# MBO.net
KiCad netlist of a schematic drawn in EAGLE
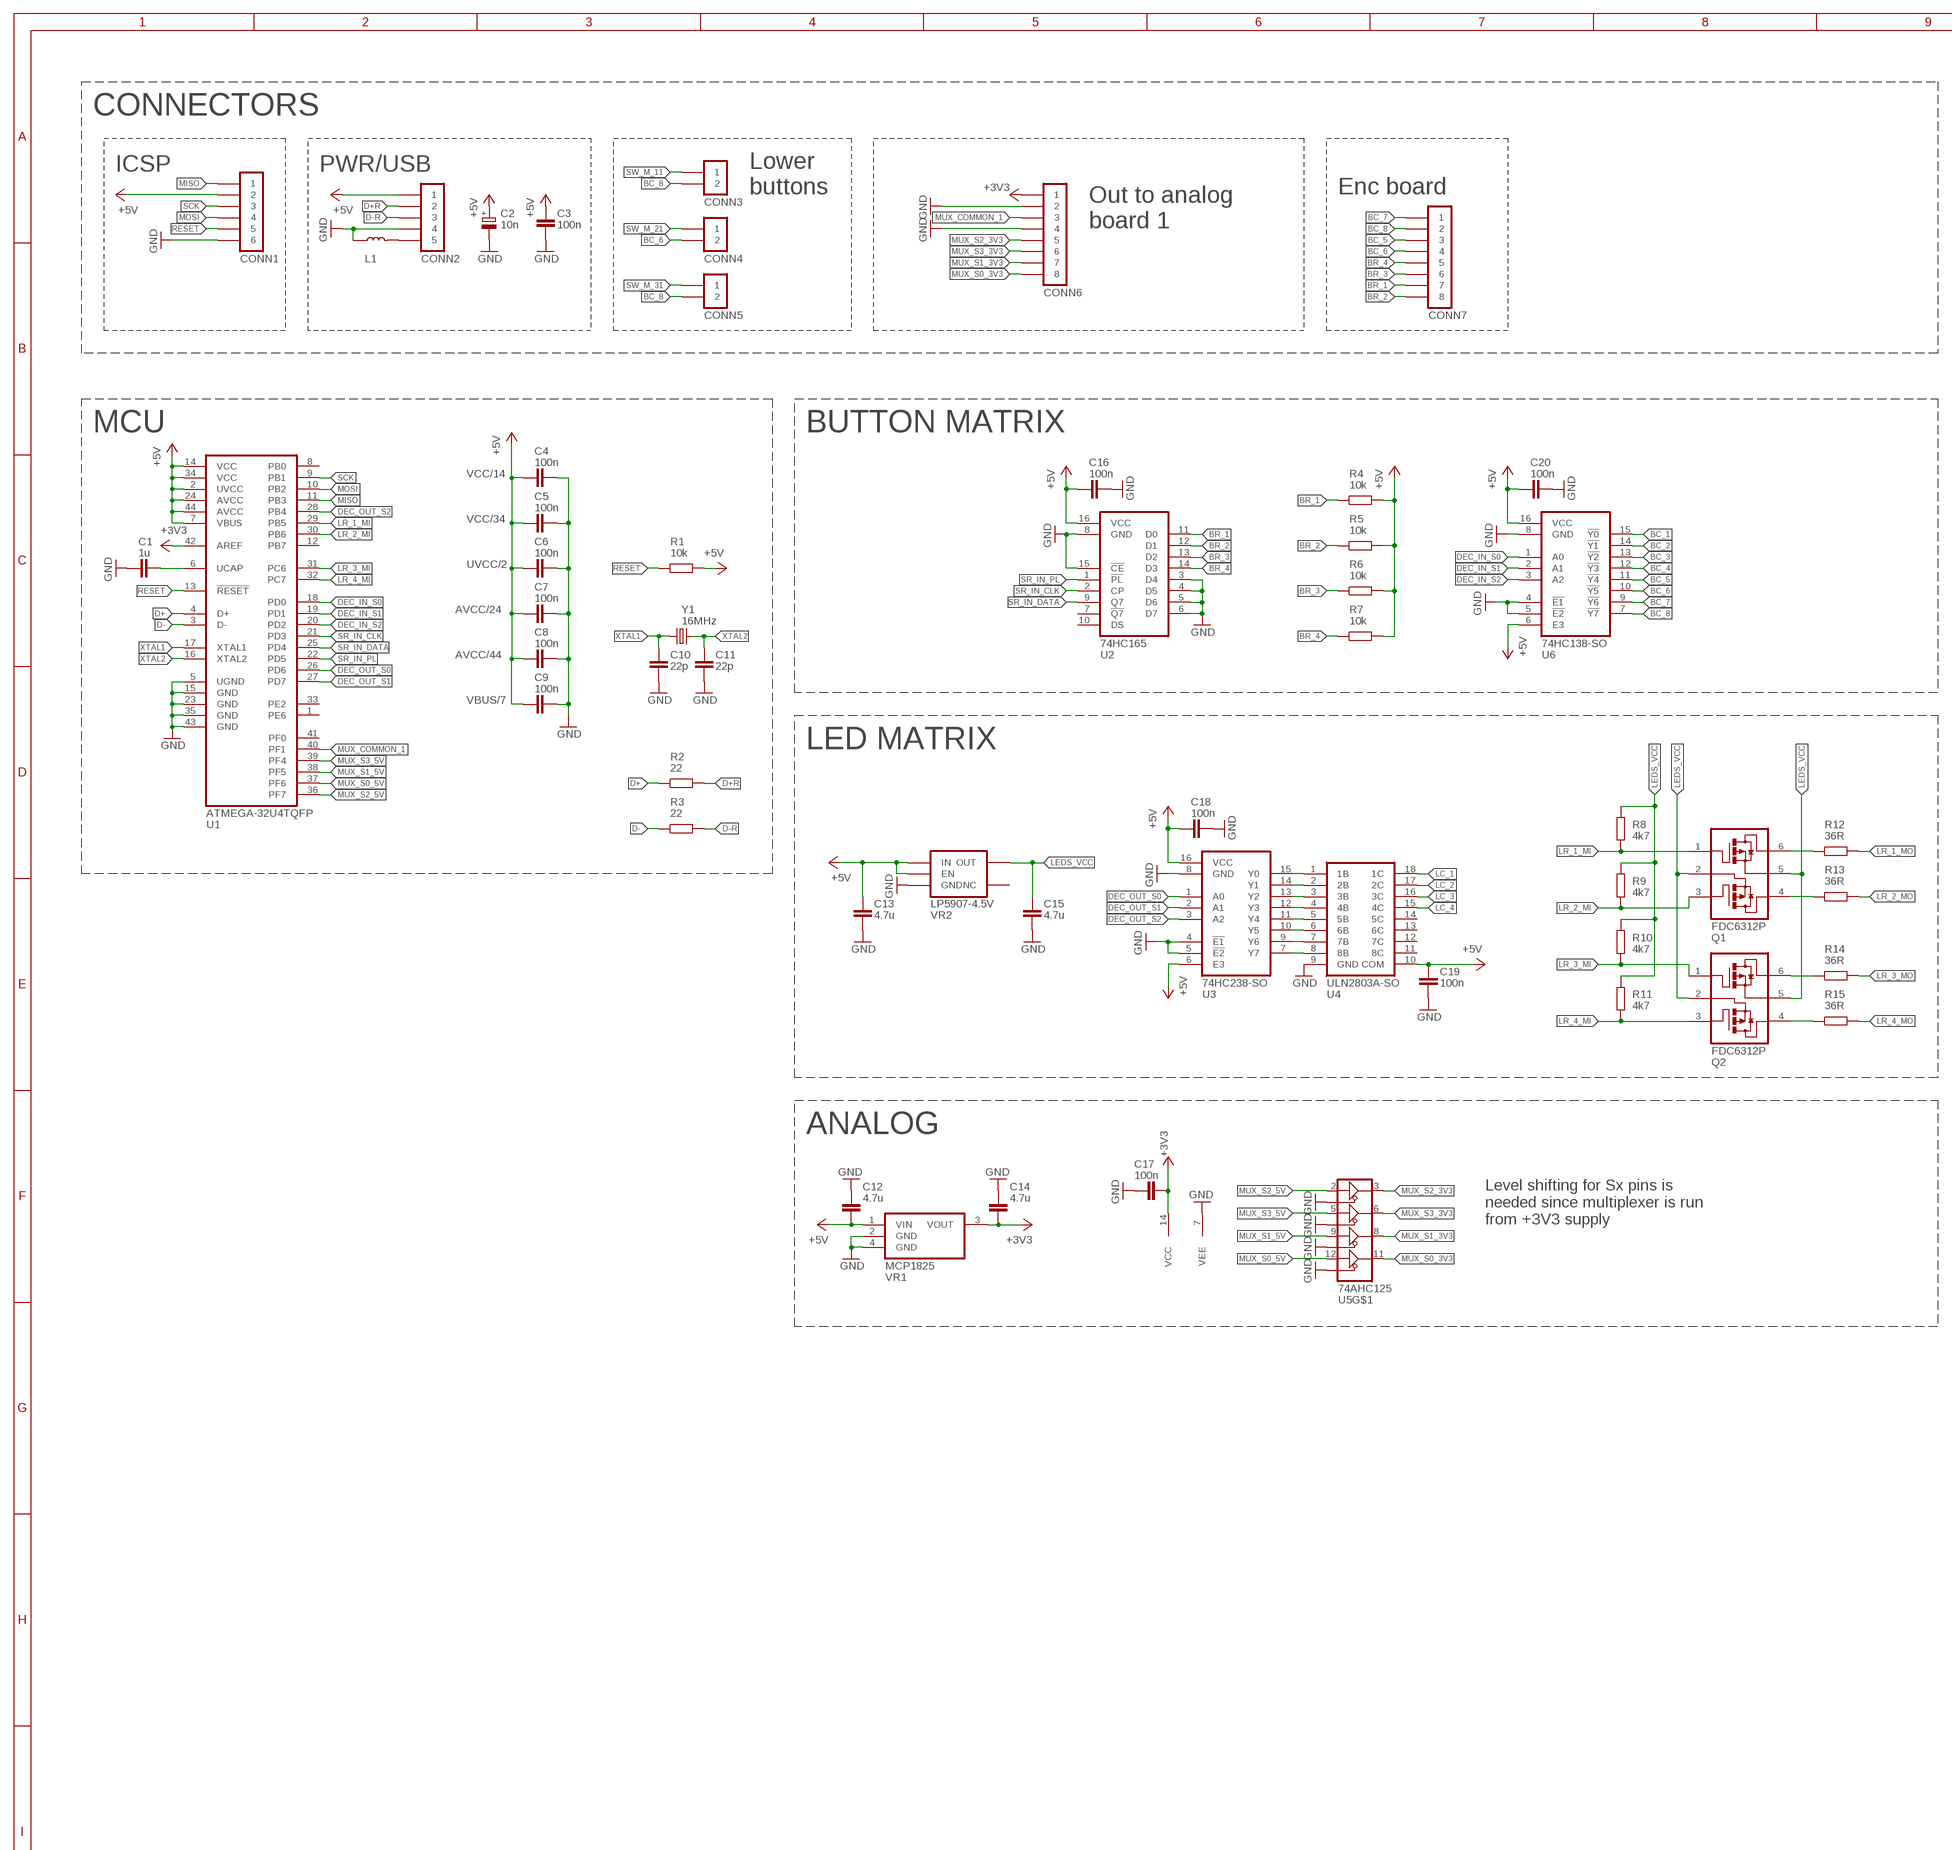
[diagram p0: schematic, sheet 1, part 1 of 2]
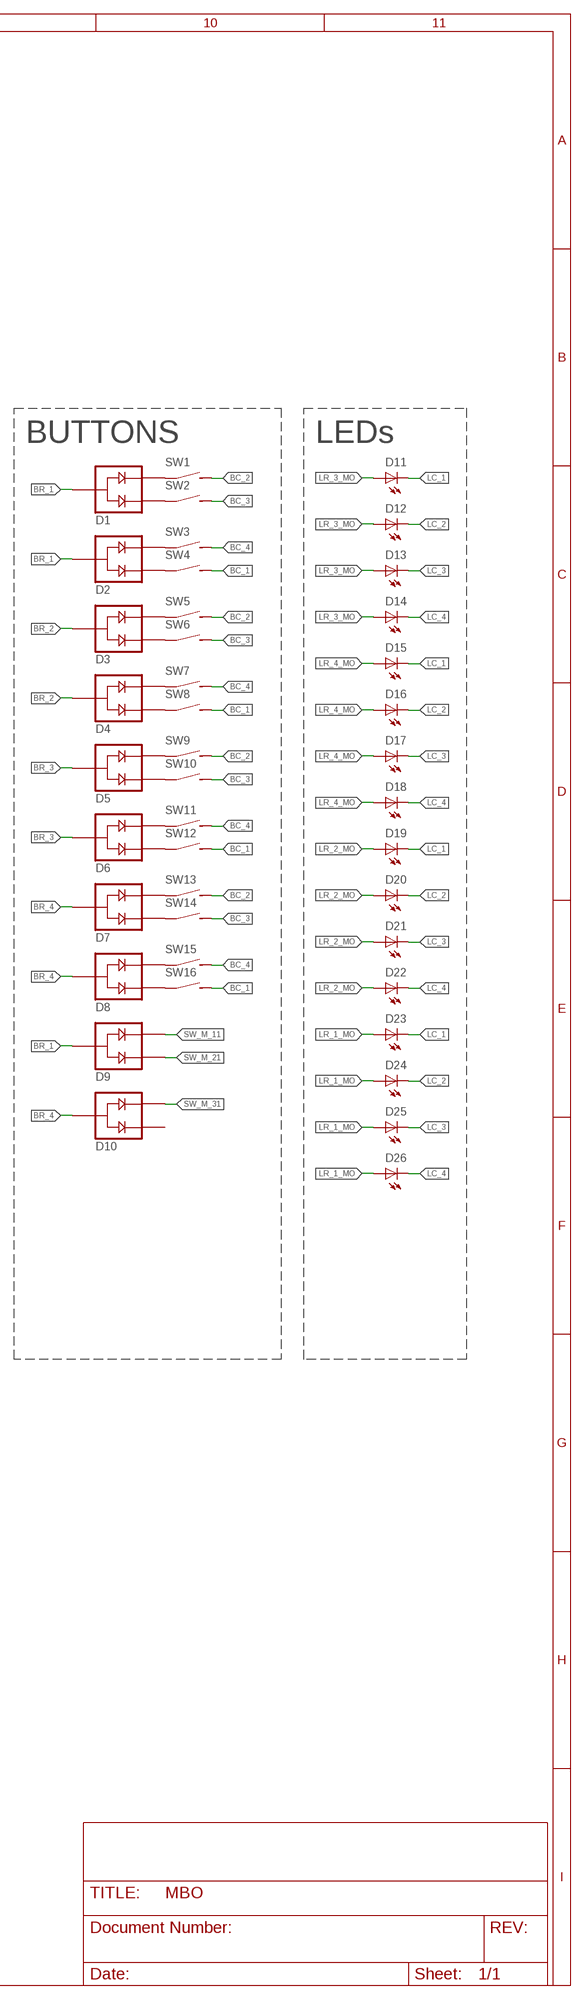
[diagram p1: schematic, sheet 1, part 2 of 2]

(export (version "E")
  (design (tool "Eeschema 10.0.6"))
  (components
    (comp (ref "C1")
      (value "1u")
      (footprint "eagle-import:C0805")
      (libsource (lib "eagle-import") (part "CAPACITOR-0805"))
    )
    (comp (ref "C2")
      (value "10n")
      (footprint "eagle-import:153CLV-0405")
      (fields (field (name "MANUFACTURER") "Multicomp") (field (name "MPN") "MCVVT016M100CA1L"))
      (libsource (lib "eagle-import") (part "ELECTROLYTIC_CAPACITOR-CLV-040516V"))
    )
    (comp (ref "C3")
      (value "100n")
      (footprint "eagle-import:C0805")
      (libsource (lib "eagle-import") (part "CAPACITOR-0805"))
    )
    (comp (ref "C4")
      (value "100n")
      (footprint "eagle-import:C0805")
      (libsource (lib "eagle-import") (part "CAPACITOR-0805"))
    )
    (comp (ref "C5")
      (value "100n")
      (footprint "eagle-import:C0805")
      (libsource (lib "eagle-import") (part "CAPACITOR-0805"))
    )
    (comp (ref "C6")
      (value "100n")
      (footprint "eagle-import:C0805")
      (libsource (lib "eagle-import") (part "CAPACITOR-0805"))
    )
    (comp (ref "C7")
      (value "100n")
      (footprint "eagle-import:C0805")
      (libsource (lib "eagle-import") (part "CAPACITOR-0805"))
    )
    (comp (ref "C8")
      (value "100n")
      (footprint "eagle-import:C0805")
      (libsource (lib "eagle-import") (part "CAPACITOR-0805"))
    )
    (comp (ref "C9")
      (value "100n")
      (footprint "eagle-import:C0805")
      (libsource (lib "eagle-import") (part "CAPACITOR-0805"))
    )
    (comp (ref "C10")
      (value "22p")
      (footprint "eagle-import:C0805")
      (libsource (lib "eagle-import") (part "CAPACITOR-0805"))
    )
    (comp (ref "C11")
      (value "22p")
      (footprint "eagle-import:C0805")
      (libsource (lib "eagle-import") (part "CAPACITOR-0805"))
    )
    (comp (ref "C12")
      (value "4.7u")
      (footprint "eagle-import:C0805")
      (libsource (lib "eagle-import") (part "CAPACITOR-0805"))
    )
    (comp (ref "C13")
      (value "4.7u")
      (footprint "eagle-import:C0805")
      (libsource (lib "eagle-import") (part "CAPACITOR-0805"))
    )
    (comp (ref "C14")
      (value "4.7u")
      (footprint "eagle-import:C0805")
      (libsource (lib "eagle-import") (part "CAPACITOR-0805"))
    )
    (comp (ref "C15")
      (value "4.7u")
      (footprint "eagle-import:C0805")
      (libsource (lib "eagle-import") (part "CAPACITOR-0805"))
    )
    (comp (ref "C16")
      (value "100n")
      (footprint "eagle-import:C0805")
      (libsource (lib "eagle-import") (part "CAPACITOR-0805"))
    )
    (comp (ref "C17")
      (value "100n")
      (footprint "eagle-import:C0805")
      (libsource (lib "eagle-import") (part "CAPACITOR-0805"))
    )
    (comp (ref "C18")
      (value "100n")
      (footprint "eagle-import:C0805")
      (libsource (lib "eagle-import") (part "CAPACITOR-0805"))
    )
    (comp (ref "C19")
      (value "100n")
      (footprint "eagle-import:C0805")
      (libsource (lib "eagle-import") (part "CAPACITOR-0805"))
    )
    (comp (ref "C20")
      (value "100n")
      (footprint "eagle-import:C0805")
      (libsource (lib "eagle-import") (part "CAPACITOR-0805"))
    )
    (comp (ref "CONN1")
      (value "PINHD-2X03-TH-2.54MM-V")
      (footprint "eagle-import:2X03-2.54-V")
      (libsource (lib "eagle-import") (part "PINHD-2X03-TH-2.54MM-V"))
    )
    (comp (ref "CONN2")
      (value "PINHD-1X05-JST-XH-H")
      (footprint "eagle-import:JST-XH-05P-H")
      (libsource (lib "eagle-import") (part "PINHD-1X05-JST-XH-H"))
    )
    (comp (ref "CONN3")
      (value "PINHD-1X02-JST-XH-H")
      (footprint "eagle-import:JST-XH-02P-H")
      (libsource (lib "eagle-import") (part "PINHD-1X02-JST-XH-H"))
    )
    (comp (ref "CONN4")
      (value "PINHD-1X02-JST-XH-H")
      (footprint "eagle-import:JST-XH-02P-H")
      (libsource (lib "eagle-import") (part "PINHD-1X02-JST-XH-H"))
    )
    (comp (ref "CONN5")
      (value "PINHD-1X02-JST-XH-H")
      (footprint "eagle-import:JST-XH-02P-H")
      (libsource (lib "eagle-import") (part "PINHD-1X02-JST-XH-H"))
    )
    (comp (ref "CONN6")
      (value "PINHD-2X04-IDC-2.54-V")
      (footprint "eagle-import:IDC-08P-2.54")
      (libsource (lib "eagle-import") (part "PINHD-2X04-IDC-2.54-V"))
    )
    (comp (ref "CONN7")
      (value "PINHD-1X08-FFC-1MM")
      (footprint "eagle-import:MOLEX-52793-0870")
      (libsource (lib "eagle-import") (part "PINHD-1X08-FFC-1MM"))
    )
    (comp (ref "D1")
      (value "BAW56")
      (footprint "eagle-import:SOT23")
      (fields (field (name "MANUFACTURER") "Multicomp") (field (name "MPN") "BAW56-7-F"))
      (libsource (lib "eagle-import") (part "BAW56"))
    )
    (comp (ref "D2")
      (value "BAW56")
      (footprint "eagle-import:SOT23")
      (fields (field (name "MANUFACTURER") "Multicomp") (field (name "MPN") "BAW56-7-F"))
      (libsource (lib "eagle-import") (part "BAW56"))
    )
    (comp (ref "D3")
      (value "BAW56")
      (footprint "eagle-import:SOT23")
      (fields (field (name "MANUFACTURER") "Multicomp") (field (name "MPN") "BAW56-7-F"))
      (libsource (lib "eagle-import") (part "BAW56"))
    )
    (comp (ref "D4")
      (value "BAW56")
      (footprint "eagle-import:SOT23")
      (fields (field (name "MANUFACTURER") "Multicomp") (field (name "MPN") "BAW56-7-F"))
      (libsource (lib "eagle-import") (part "BAW56"))
    )
    (comp (ref "D5")
      (value "BAW56")
      (footprint "eagle-import:SOT23")
      (fields (field (name "MANUFACTURER") "Multicomp") (field (name "MPN") "BAW56-7-F"))
      (libsource (lib "eagle-import") (part "BAW56"))
    )
    (comp (ref "D6")
      (value "BAW56")
      (footprint "eagle-import:SOT23")
      (fields (field (name "MANUFACTURER") "Multicomp") (field (name "MPN") "BAW56-7-F"))
      (libsource (lib "eagle-import") (part "BAW56"))
    )
    (comp (ref "D7")
      (value "BAW56")
      (footprint "eagle-import:SOT23")
      (fields (field (name "MANUFACTURER") "Multicomp") (field (name "MPN") "BAW56-7-F"))
      (libsource (lib "eagle-import") (part "BAW56"))
    )
    (comp (ref "D8")
      (value "BAW56")
      (footprint "eagle-import:SOT23")
      (fields (field (name "MANUFACTURER") "Multicomp") (field (name "MPN") "BAW56-7-F"))
      (libsource (lib "eagle-import") (part "BAW56"))
    )
    (comp (ref "D9")
      (value "BAW56")
      (footprint "eagle-import:SOT23")
      (fields (field (name "MANUFACTURER") "Multicomp") (field (name "MPN") "BAW56-7-F"))
      (libsource (lib "eagle-import") (part "BAW56"))
    )
    (comp (ref "D10")
      (value "BAW56")
      (footprint "eagle-import:SOT23")
      (fields (field (name "MANUFACTURER") "Multicomp") (field (name "MPN") "BAW56-7-F"))
      (libsource (lib "eagle-import") (part "BAW56"))
    )
    (comp (ref "D11")
      (value "LED-0805")
      (footprint "eagle-import:0805_LED")
      (libsource (lib "eagle-import") (part "LED-0805"))
    )
    (comp (ref "D12")
      (value "LED-0805")
      (footprint "eagle-import:0805_LED")
      (libsource (lib "eagle-import") (part "LED-0805"))
    )
    (comp (ref "D13")
      (value "LED-0805")
      (footprint "eagle-import:0805_LED")
      (libsource (lib "eagle-import") (part "LED-0805"))
    )
    (comp (ref "D14")
      (value "LED-0805")
      (footprint "eagle-import:0805_LED")
      (libsource (lib "eagle-import") (part "LED-0805"))
    )
    (comp (ref "D15")
      (value "LED-0805")
      (footprint "eagle-import:0805_LED")
      (libsource (lib "eagle-import") (part "LED-0805"))
    )
    (comp (ref "D16")
      (value "LED-0805")
      (footprint "eagle-import:0805_LED")
      (libsource (lib "eagle-import") (part "LED-0805"))
    )
    (comp (ref "D17")
      (value "LED-0805")
      (footprint "eagle-import:0805_LED")
      (libsource (lib "eagle-import") (part "LED-0805"))
    )
    (comp (ref "D18")
      (value "LED-0805")
      (footprint "eagle-import:0805_LED")
      (libsource (lib "eagle-import") (part "LED-0805"))
    )
    (comp (ref "D19")
      (value "LED-0805")
      (footprint "eagle-import:0805_LED")
      (libsource (lib "eagle-import") (part "LED-0805"))
    )
    (comp (ref "D20")
      (value "LED-0805")
      (footprint "eagle-import:0805_LED")
      (libsource (lib "eagle-import") (part "LED-0805"))
    )
    (comp (ref "D21")
      (value "LED-0805")
      (footprint "eagle-import:0805_LED")
      (libsource (lib "eagle-import") (part "LED-0805"))
    )
    (comp (ref "D22")
      (value "LED-0805")
      (footprint "eagle-import:0805_LED")
      (libsource (lib "eagle-import") (part "LED-0805"))
    )
    (comp (ref "D23")
      (value "LED-0805")
      (footprint "eagle-import:0805_LED")
      (libsource (lib "eagle-import") (part "LED-0805"))
    )
    (comp (ref "D24")
      (value "LED-0805")
      (footprint "eagle-import:0805_LED")
      (libsource (lib "eagle-import") (part "LED-0805"))
    )
    (comp (ref "D25")
      (value "LED-0805")
      (footprint "eagle-import:0805_LED")
      (libsource (lib "eagle-import") (part "LED-0805"))
    )
    (comp (ref "D26")
      (value "LED-0805")
      (footprint "eagle-import:0805_LED")
      (libsource (lib "eagle-import") (part "LED-0805"))
    )
    (comp (ref "L1")
      (value "INDUCTOR-0805")
      (footprint "eagle-import:L0805")
      (libsource (lib "eagle-import") (part "INDUCTOR-0805"))
    )
    (comp (ref "Q1")
      (value "FDC6312P")
      (footprint "eagle-import:SSOT6")
      (fields (field (name "MANUFACTURER") "ON Semiconductor"))
      (libsource (lib "eagle-import") (part "FDC6312P"))
    )
    (comp (ref "Q2")
      (value "FDC6312P")
      (footprint "eagle-import:SSOT6")
      (fields (field (name "MANUFACTURER") "ON Semiconductor"))
      (libsource (lib "eagle-import") (part "FDC6312P"))
    )
    (comp (ref "R1")
      (value "10k")
      (footprint "eagle-import:R0805")
      (libsource (lib "eagle-import") (part "RESISTOR-0805"))
    )
    (comp (ref "R2")
      (value "22")
      (footprint "eagle-import:R0805")
      (libsource (lib "eagle-import") (part "RESISTOR-0805"))
    )
    (comp (ref "R3")
      (value "22")
      (footprint "eagle-import:R0805")
      (libsource (lib "eagle-import") (part "RESISTOR-0805"))
    )
    (comp (ref "R4")
      (value "10k")
      (footprint "eagle-import:R0805")
      (libsource (lib "eagle-import") (part "RESISTOR-0805"))
    )
    (comp (ref "R5")
      (value "10k")
      (footprint "eagle-import:R0805")
      (libsource (lib "eagle-import") (part "RESISTOR-0805"))
    )
    (comp (ref "R6")
      (value "10k")
      (footprint "eagle-import:R0805")
      (libsource (lib "eagle-import") (part "RESISTOR-0805"))
    )
    (comp (ref "R7")
      (value "10k")
      (footprint "eagle-import:R0805")
      (libsource (lib "eagle-import") (part "RESISTOR-0805"))
    )
    (comp (ref "R8")
      (value "4k7")
      (footprint "eagle-import:R0805")
      (libsource (lib "eagle-import") (part "RESISTOR-0805"))
    )
    (comp (ref "R9")
      (value "4k7")
      (footprint "eagle-import:R0805")
      (libsource (lib "eagle-import") (part "RESISTOR-0805"))
    )
    (comp (ref "R10")
      (value "4k7")
      (footprint "eagle-import:R0805")
      (libsource (lib "eagle-import") (part "RESISTOR-0805"))
    )
    (comp (ref "R11")
      (value "4k7")
      (footprint "eagle-import:R0805")
      (libsource (lib "eagle-import") (part "RESISTOR-0805"))
    )
    (comp (ref "R12")
      (value "36R")
      (footprint "eagle-import:R0805")
      (libsource (lib "eagle-import") (part "RESISTOR-0805"))
    )
    (comp (ref "R13")
      (value "36R")
      (footprint "eagle-import:R0805")
      (libsource (lib "eagle-import") (part "RESISTOR-0805"))
    )
    (comp (ref "R14")
      (value "36R")
      (footprint "eagle-import:R0805")
      (libsource (lib "eagle-import") (part "RESISTOR-0805"))
    )
    (comp (ref "R15")
      (value "36R")
      (footprint "eagle-import:R0805")
      (libsource (lib "eagle-import") (part "RESISTOR-0805"))
    )
    (comp (ref "SW1")
      (value "SWITCH-RUBBER2")
      (footprint "eagle-import:RUBBER_SWITCH_2")
      (libsource (lib "eagle-import") (part "SWITCH-RUBBER2"))
    )
    (comp (ref "SW2")
      (value "SWITCH-RUBBER2")
      (footprint "eagle-import:RUBBER_SWITCH_2")
      (libsource (lib "eagle-import") (part "SWITCH-RUBBER2"))
    )
    (comp (ref "SW3")
      (value "SWITCH-RUBBER2")
      (footprint "eagle-import:RUBBER_SWITCH_2")
      (libsource (lib "eagle-import") (part "SWITCH-RUBBER2"))
    )
    (comp (ref "SW4")
      (value "SWITCH-RUBBER2")
      (footprint "eagle-import:RUBBER_SWITCH_2")
      (libsource (lib "eagle-import") (part "SWITCH-RUBBER2"))
    )
    (comp (ref "SW5")
      (value "SWITCH-RUBBER2")
      (footprint "eagle-import:RUBBER_SWITCH_2")
      (libsource (lib "eagle-import") (part "SWITCH-RUBBER2"))
    )
    (comp (ref "SW6")
      (value "SWITCH-RUBBER2")
      (footprint "eagle-import:RUBBER_SWITCH_2")
      (libsource (lib "eagle-import") (part "SWITCH-RUBBER2"))
    )
    (comp (ref "SW7")
      (value "SWITCH-RUBBER2")
      (footprint "eagle-import:RUBBER_SWITCH_2")
      (libsource (lib "eagle-import") (part "SWITCH-RUBBER2"))
    )
    (comp (ref "SW8")
      (value "SWITCH-RUBBER2")
      (footprint "eagle-import:RUBBER_SWITCH_2")
      (libsource (lib "eagle-import") (part "SWITCH-RUBBER2"))
    )
    (comp (ref "SW9")
      (value "SWITCH-RUBBER2")
      (footprint "eagle-import:RUBBER_SWITCH_2")
      (libsource (lib "eagle-import") (part "SWITCH-RUBBER2"))
    )
    (comp (ref "SW10")
      (value "SWITCH-RUBBER2")
      (footprint "eagle-import:RUBBER_SWITCH_2")
      (libsource (lib "eagle-import") (part "SWITCH-RUBBER2"))
    )
    (comp (ref "SW11")
      (value "SWITCH-RUBBER2")
      (footprint "eagle-import:RUBBER_SWITCH_2")
      (libsource (lib "eagle-import") (part "SWITCH-RUBBER2"))
    )
    (comp (ref "SW12")
      (value "SWITCH-RUBBER2")
      (footprint "eagle-import:RUBBER_SWITCH_2")
      (libsource (lib "eagle-import") (part "SWITCH-RUBBER2"))
    )
    (comp (ref "SW13")
      (value "SWITCH-RUBBER2")
      (footprint "eagle-import:RUBBER_SWITCH_2")
      (libsource (lib "eagle-import") (part "SWITCH-RUBBER2"))
    )
    (comp (ref "SW14")
      (value "SWITCH-RUBBER2")
      (footprint "eagle-import:RUBBER_SWITCH_2")
      (libsource (lib "eagle-import") (part "SWITCH-RUBBER2"))
    )
    (comp (ref "SW15")
      (value "SWITCH-RUBBER2")
      (footprint "eagle-import:RUBBER_SWITCH_2")
      (libsource (lib "eagle-import") (part "SWITCH-RUBBER2"))
    )
    (comp (ref "SW16")
      (value "SWITCH-RUBBER2")
      (footprint "eagle-import:RUBBER_SWITCH_2")
      (libsource (lib "eagle-import") (part "SWITCH-RUBBER2"))
    )
    (comp (ref "U1")
      (value "ATMEGA-32U4TQFP")
      (footprint "eagle-import:TQFP-44")
      (fields (field (name "MPN") "ATMEGA32U4-AUR"))
      (libsource (lib "eagle-import") (part "ATMEGA-32U4TQFP"))
    )
    (comp (ref "U2")
      (value "74HC165")
      (footprint "eagle-import:SO16")
      (fields (field (name "MANUFACTURER") "Nexperia") (field (name "MPN") "74HC165D"))
      (libsource (lib "eagle-import") (part "74165HC"))
    )
    (comp (ref "U3")
      (value "74HC238-SO")
      (footprint "eagle-import:SO16")
      (fields (field (name "MANUFACTURER") "Nexperia") (field (name "MPN") "74HC238D"))
      (libsource (lib "eagle-import") (part "74238-SOHC"))
    )
    (comp (ref "U4")
      (value "ULN2803A-SO")
      (footprint "eagle-import:SO18")
      (fields (field (name "MANUFACTURER") "Texas Instruments") (field (name "MPN") "ULN2803ADWR"))
      (libsource (lib "eagle-import") (part "ULN2803A-SO"))
    )
    (comp (ref "U5")
      (value "74AHC125")
      (footprint "eagle-import:SOIC14")
      (fields (field (name "MANUFACTURER") "Texas Instruments") (field (name "MPN") "SN74AHC125DR"))
      (libsource (lib "eagle-import") (part "74AHC125"))
    )
    (comp (ref "U6")
      (value "74HC138-SO")
      (footprint "eagle-import:SO16")
      (fields (field (name "MANUFACTURER") "Nexperia") (field (name "MPN") "74HC138D"))
      (libsource (lib "eagle-import") (part "74138-SOHC"))
    )
    (comp (ref "VR1")
      (value "MCP1825")
      (footprint "eagle-import:SOT223")
      (fields (field (name "MANUFACTURER") "Microchip") (field (name "MPN") "MCP1825S-3302E/DB"))
      (libsource (lib "eagle-import") (part "MCP1825"))
    )
    (comp (ref "VR2")
      (value "LP5907-4.5V")
      (footprint "eagle-import:SOT23-5")
      (fields (field (name "MANUFACTURER") "Texas Instruments") (field (name "MPN") "LP5907MFX-4.5/NOPB"))
      (libsource (lib "eagle-import") (part "LP5907-4.5V"))
    )
    (comp (ref "Y1")
      (value "16MHz")
      (footprint "eagle-import:HC49US")
      (fields (field (name "MANUFACTURER") "TXC") (field (name "MPN") "9B-8.000MEEJ-B"))
      (libsource (lib "eagle-import") (part "CRYSTAL"))
    )
  )
  (nets
    (net (code "1") (name "+3V3") (class "Default")
      (node (ref "C14") (pin "1") (pinfunction "1_1") (pintype "passive"))
      (node (ref "C17") (pin "1") (pinfunction "1_1") (pintype "passive"))
      (node (ref "CONN6") (pin "1") (pinfunction "1_1") (pintype "passive"))
      (node (ref "U1") (pin "42") (pinfunction "AREF_42") (pintype "passive"))
      (node (ref "U5") (pin "14") (pinfunction "VCC_14") (pintype "passive"))
      (node (ref "VR1") (pin "3") (pinfunction "VOUT_3") (pintype "passive"))
    )
    (net (code "2") (name "+5V") (class "Default")
      (node (ref "C12") (pin "1") (pinfunction "1_1") (pintype "passive"))
      (node (ref "C13") (pin "1") (pinfunction "1_1") (pintype "passive"))
      (node (ref "C16") (pin "2") (pinfunction "2_2") (pintype "passive"))
      (node (ref "C18") (pin "2") (pinfunction "2_2") (pintype "passive"))
      (node (ref "C19") (pin "2") (pinfunction "2_2") (pintype "passive"))
      (node (ref "C2") (pin "+") (pinfunction "+_+") (pintype "passive"))
      (node (ref "C20") (pin "2") (pinfunction "2_2") (pintype "passive"))
      (node (ref "C3") (pin "1") (pinfunction "1_1") (pintype "passive"))
      (node (ref "C4") (pin "1") (pinfunction "1_1") (pintype "passive"))
      (node (ref "C5") (pin "1") (pinfunction "1_1") (pintype "passive"))
      (node (ref "C6") (pin "1") (pinfunction "1_1") (pintype "passive"))
      (node (ref "C7") (pin "1") (pinfunction "1_1") (pintype "passive"))
      (node (ref "C8") (pin "1") (pinfunction "1_1") (pintype "passive"))
      (node (ref "C9") (pin "1") (pinfunction "1_1") (pintype "passive"))
      (node (ref "CONN1") (pin "2") (pinfunction "2_2") (pintype "passive"))
      (node (ref "CONN2") (pin "1") (pinfunction "1_1") (pintype "passive"))
      (node (ref "R1") (pin "2") (pinfunction "2_2") (pintype "passive"))
      (node (ref "R4") (pin "2") (pinfunction "2_2") (pintype "passive"))
      (node (ref "R5") (pin "2") (pinfunction "2_2") (pintype "passive"))
      (node (ref "R6") (pin "2") (pinfunction "2_2") (pintype "passive"))
      (node (ref "R7") (pin "2") (pinfunction "2_2") (pintype "passive"))
      (node (ref "U1") (pin "14") (pinfunction "VCC_14") (pintype "passive"))
      (node (ref "U1") (pin "2") (pinfunction "UVCC_2") (pintype "passive"))
      (node (ref "U1") (pin "24") (pinfunction "AVCC_24") (pintype "passive"))
      (node (ref "U1") (pin "34") (pinfunction "VCC_34") (pintype "passive"))
      (node (ref "U1") (pin "44") (pinfunction "AVCC_44") (pintype "passive"))
      (node (ref "U1") (pin "7") (pinfunction "VBUS_7") (pintype "passive"))
      (node (ref "U2") (pin "16") (pinfunction "VCC_16") (pintype "power_in"))
      (node (ref "U3") (pin "16") (pinfunction "VCC_16") (pintype "power_in"))
      (node (ref "U3") (pin "6") (pinfunction "E3_6") (pintype "input"))
      (node (ref "U4") (pin "10") (pinfunction "COM_10") (pintype "passive"))
      (node (ref "U6") (pin "16") (pinfunction "VCC_16") (pintype "power_in"))
      (node (ref "U6") (pin "6") (pinfunction "E3_6") (pintype "input"))
      (node (ref "VR1") (pin "1") (pinfunction "VIN_1") (pintype "passive"))
      (node (ref "VR2") (pin "1") (pinfunction "IN_1") (pintype "power_in"))
      (node (ref "VR2") (pin "3") (pinfunction "EN_3") (pintype "input"))
    )
    (net (code "3") (name "BC_1") (class "Default")
      (node (ref "SW12") (pin "2") (pinfunction "2_2") (pintype "passive"))
      (node (ref "SW16") (pin "2") (pinfunction "2_2") (pintype "passive"))
      (node (ref "SW4") (pin "2") (pinfunction "2_2") (pintype "passive"))
      (node (ref "SW8") (pin "2") (pinfunction "2_2") (pintype "passive"))
      (node (ref "U6") (pin "15") (pinfunction "~{Y0}_15") (pintype "output"))
    )
    (net (code "4") (name "BC_2") (class "Default")
      (node (ref "SW1") (pin "2") (pinfunction "2_2") (pintype "passive"))
      (node (ref "SW13") (pin "2") (pinfunction "2_2") (pintype "passive"))
      (node (ref "SW5") (pin "2") (pinfunction "2_2") (pintype "passive"))
      (node (ref "SW9") (pin "2") (pinfunction "2_2") (pintype "passive"))
      (node (ref "U6") (pin "14") (pinfunction "~{Y1}_14") (pintype "output"))
    )
    (net (code "5") (name "BC_3") (class "Default")
      (node (ref "SW10") (pin "2") (pinfunction "2_2") (pintype "passive"))
      (node (ref "SW14") (pin "2") (pinfunction "2_2") (pintype "passive"))
      (node (ref "SW2") (pin "2") (pinfunction "2_2") (pintype "passive"))
      (node (ref "SW6") (pin "2") (pinfunction "2_2") (pintype "passive"))
      (node (ref "U6") (pin "13") (pinfunction "~{Y2}_13") (pintype "output"))
    )
    (net (code "6") (name "BC_4") (class "Default")
      (node (ref "SW11") (pin "2") (pinfunction "2_2") (pintype "passive"))
      (node (ref "SW15") (pin "2") (pinfunction "2_2") (pintype "passive"))
      (node (ref "SW3") (pin "2") (pinfunction "2_2") (pintype "passive"))
      (node (ref "SW7") (pin "2") (pinfunction "2_2") (pintype "passive"))
      (node (ref "U6") (pin "12") (pinfunction "~{Y3}_12") (pintype "output"))
    )
    (net (code "7") (name "BC_5") (class "Default")
      (node (ref "CONN7") (pin "3") (pinfunction "3_3") (pintype "passive"))
      (node (ref "U6") (pin "11") (pinfunction "~{Y4}_11") (pintype "output"))
    )
    (net (code "8") (name "BC_6") (class "Default")
      (node (ref "CONN4") (pin "2") (pinfunction "2_2") (pintype "passive"))
      (node (ref "CONN7") (pin "4") (pinfunction "4_4") (pintype "passive"))
      (node (ref "U6") (pin "10") (pinfunction "~{Y5}_10") (pintype "output"))
    )
    (net (code "9") (name "BC_7") (class "Default")
      (node (ref "CONN7") (pin "1") (pinfunction "1_1") (pintype "passive"))
      (node (ref "U6") (pin "9") (pinfunction "~{Y6}_9") (pintype "output"))
    )
    (net (code "10") (name "BC_8") (class "Default")
      (node (ref "CONN3") (pin "2") (pinfunction "2_2") (pintype "passive"))
      (node (ref "CONN5") (pin "2") (pinfunction "2_2") (pintype "passive"))
      (node (ref "CONN7") (pin "2") (pinfunction "2_2") (pintype "passive"))
      (node (ref "U6") (pin "7") (pinfunction "~{Y7}_7") (pintype "output"))
    )
    (net (code "11") (name "BR_1") (class "Default")
      (node (ref "CONN7") (pin "7") (pinfunction "7_7") (pintype "passive"))
      (node (ref "D1") (pin "3") (pinfunction "3_3") (pintype "passive"))
      (node (ref "D2") (pin "3") (pinfunction "3_3") (pintype "passive"))
      (node (ref "D9") (pin "3") (pinfunction "3_3") (pintype "passive"))
      (node (ref "R4") (pin "1") (pinfunction "1_1") (pintype "passive"))
      (node (ref "U2") (pin "11") (pinfunction "D0_11") (pintype "input"))
    )
    (net (code "12") (name "BR_2") (class "Default")
      (node (ref "CONN7") (pin "8") (pinfunction "8_8") (pintype "passive"))
      (node (ref "D3") (pin "3") (pinfunction "3_3") (pintype "passive"))
      (node (ref "D4") (pin "3") (pinfunction "3_3") (pintype "passive"))
      (node (ref "R5") (pin "1") (pinfunction "1_1") (pintype "passive"))
      (node (ref "U2") (pin "12") (pinfunction "D1_12") (pintype "input"))
    )
    (net (code "13") (name "BR_3") (class "Default")
      (node (ref "CONN7") (pin "6") (pinfunction "6_6") (pintype "passive"))
      (node (ref "D5") (pin "3") (pinfunction "3_3") (pintype "passive"))
      (node (ref "D6") (pin "3") (pinfunction "3_3") (pintype "passive"))
      (node (ref "R6") (pin "1") (pinfunction "1_1") (pintype "passive"))
      (node (ref "U2") (pin "13") (pinfunction "D2_13") (pintype "input"))
    )
    (net (code "14") (name "BR_4") (class "Default")
      (node (ref "CONN7") (pin "5") (pinfunction "5_5") (pintype "passive"))
      (node (ref "D10") (pin "3") (pinfunction "3_3") (pintype "passive"))
      (node (ref "D7") (pin "3") (pinfunction "3_3") (pintype "passive"))
      (node (ref "D8") (pin "3") (pinfunction "3_3") (pintype "passive"))
      (node (ref "R7") (pin "1") (pinfunction "1_1") (pintype "passive"))
      (node (ref "U2") (pin "14") (pinfunction "D3_14") (pintype "input"))
    )
    (net (code "15") (name "D+") (class "Default")
      (node (ref "R2") (pin "1") (pinfunction "1_1") (pintype "passive"))
      (node (ref "U1") (pin "4") (pinfunction "D+_4") (pintype "bidirectional"))
    )
    (net (code "16") (name "D+R") (class "Default")
      (node (ref "CONN2") (pin "2") (pinfunction "2_2") (pintype "passive"))
      (node (ref "R2") (pin "2") (pinfunction "2_2") (pintype "passive"))
    )
    (net (code "17") (name "D-") (class "Default")
      (node (ref "R3") (pin "1") (pinfunction "1_1") (pintype "passive"))
      (node (ref "U1") (pin "3") (pinfunction "D-_3") (pintype "bidirectional"))
    )
    (net (code "18") (name "D-R") (class "Default")
      (node (ref "CONN2") (pin "3") (pinfunction "3_3") (pintype "passive"))
      (node (ref "R3") (pin "2") (pinfunction "2_2") (pintype "passive"))
    )
    (net (code "19") (name "DEC_IN_S0") (class "Default")
      (node (ref "U1") (pin "18") (pinfunction "PD0_18") (pintype "bidirectional"))
      (node (ref "U6") (pin "1") (pinfunction "A0_1") (pintype "input"))
    )
    (net (code "20") (name "DEC_IN_S1") (class "Default")
      (node (ref "U1") (pin "19") (pinfunction "PD1_19") (pintype "bidirectional"))
      (node (ref "U6") (pin "2") (pinfunction "A1_2") (pintype "input"))
    )
    (net (code "21") (name "DEC_IN_S2") (class "Default")
      (node (ref "U1") (pin "20") (pinfunction "PD2_20") (pintype "bidirectional"))
      (node (ref "U6") (pin "3") (pinfunction "A2_3") (pintype "input"))
    )
    (net (code "22") (name "DEC_OUT_S0") (class "Default")
      (node (ref "U1") (pin "26") (pinfunction "PD6_26") (pintype "bidirectional"))
      (node (ref "U3") (pin "1") (pinfunction "A0_1") (pintype "input"))
    )
    (net (code "23") (name "DEC_OUT_S1") (class "Default")
      (node (ref "U1") (pin "27") (pinfunction "PD7_27") (pintype "bidirectional"))
      (node (ref "U3") (pin "2") (pinfunction "A1_2") (pintype "input"))
    )
    (net (code "24") (name "DEC_OUT_S2") (class "Default")
      (node (ref "U1") (pin "28") (pinfunction "PB4_28") (pintype "bidirectional"))
      (node (ref "U3") (pin "3") (pinfunction "A2_3") (pintype "input"))
    )
    (net (code "25") (name "GND") (class "Default")
      (node (ref "C1") (pin "2") (pinfunction "2_2") (pintype "passive"))
      (node (ref "C10") (pin "1") (pinfunction "1_1") (pintype "passive"))
      (node (ref "C11") (pin "1") (pinfunction "1_1") (pintype "passive"))
      (node (ref "C12") (pin "2") (pinfunction "2_2") (pintype "passive"))
      (node (ref "C13") (pin "2") (pinfunction "2_2") (pintype "passive"))
      (node (ref "C14") (pin "2") (pinfunction "2_2") (pintype "passive"))
      (node (ref "C15") (pin "2") (pinfunction "2_2") (pintype "passive"))
      (node (ref "C16") (pin "1") (pinfunction "1_1") (pintype "passive"))
      (node (ref "C17") (pin "2") (pinfunction "2_2") (pintype "passive"))
      (node (ref "C18") (pin "1") (pinfunction "1_1") (pintype "passive"))
      (node (ref "C19") (pin "1") (pinfunction "1_1") (pintype "passive"))
      (node (ref "C2") (pin "-") (pinfunction "-_-") (pintype "passive"))
      (node (ref "C20") (pin "1") (pinfunction "1_1") (pintype "passive"))
      (node (ref "C3") (pin "2") (pinfunction "2_2") (pintype "passive"))
      (node (ref "C4") (pin "2") (pinfunction "2_2") (pintype "passive"))
      (node (ref "C5") (pin "2") (pinfunction "2_2") (pintype "passive"))
      (node (ref "C6") (pin "2") (pinfunction "2_2") (pintype "passive"))
      (node (ref "C7") (pin "2") (pinfunction "2_2") (pintype "passive"))
      (node (ref "C8") (pin "2") (pinfunction "2_2") (pintype "passive"))
      (node (ref "C9") (pin "2") (pinfunction "2_2") (pintype "passive"))
      (node (ref "CONN1") (pin "6") (pinfunction "6_6") (pintype "passive"))
      (node (ref "CONN2") (pin "4") (pinfunction "4_4") (pintype "passive"))
      (node (ref "CONN6") (pin "2") (pinfunction "2_2") (pintype "passive"))
      (node (ref "CONN6") (pin "4") (pinfunction "4_4") (pintype "passive"))
      (node (ref "L1") (pin "1") (pinfunction "1_1") (pintype "passive"))
      (node (ref "U1") (pin "15") (pinfunction "GND_15") (pintype "passive"))
      (node (ref "U1") (pin "23") (pinfunction "GND_23") (pintype "passive"))
      (node (ref "U1") (pin "35") (pinfunction "GND_35") (pintype "passive"))
      (node (ref "U1") (pin "43") (pinfunction "GND_43") (pintype "passive"))
      (node (ref "U1") (pin "5") (pinfunction "UGND_5") (pintype "passive"))
      (node (ref "U2") (pin "15") (pinfunction "~{CE}_15") (pintype "input"))
      (node (ref "U2") (pin "3") (pinfunction "D4_3") (pintype "input"))
      (node (ref "U2") (pin "4") (pinfunction "D5_4") (pintype "input"))
      (node (ref "U2") (pin "5") (pinfunction "D6_5") (pintype "input"))
      (node (ref "U2") (pin "6") (pinfunction "D7_6") (pintype "input"))
      (node (ref "U2") (pin "8") (pinfunction "GND_8") (pintype "power_in"))
      (node (ref "U3") (pin "4") (pinfunction "~{E1}_4") (pintype "input"))
      (node (ref "U3") (pin "5") (pinfunction "~{E2}_5") (pintype "input"))
      (node (ref "U3") (pin "8") (pinfunction "GND_8") (pintype "power_in"))
      (node (ref "U4") (pin "9") (pinfunction "GND_9") (pintype "power_in"))
      (node (ref "U5") (pin "1") (pinfunction "1~{(OE})_1") (pintype "bidirectional"))
      (node (ref "U5") (pin "10") (pinfunction "3~{(OE})_10") (pintype "bidirectional"))
      (node (ref "U5") (pin "13") (pinfunction "4~{(OE})_13") (pintype "bidirectional"))
      (node (ref "U5") (pin "4") (pinfunction "2~{(OE})_4") (pintype "bidirectional"))
      (node (ref "U5") (pin "7") (pinfunction "VEE_7") (pintype "passive"))
      (node (ref "U6") (pin "4") (pinfunction "~{E1}_4") (pintype "input"))
      (node (ref "U6") (pin "5") (pinfunction "~{E2}_5") (pintype "input"))
      (node (ref "U6") (pin "8") (pinfunction "GND_8") (pintype "power_in"))
      (node (ref "VR1") (pin "2") (pinfunction "GND_2") (pintype "passive"))
      (node (ref "VR1") (pin "4") (pinfunction "GND_4") (pintype "passive"))
      (node (ref "VR2") (pin "2") (pinfunction "GND_2") (pintype "power_in"))
    )
    (net (code "26") (name "LC_1") (class "Default")
      (node (ref "D11") (pin "C") (pinfunction "C_C") (pintype "passive"))
      (node (ref "D15") (pin "C") (pinfunction "C_C") (pintype "passive"))
      (node (ref "D19") (pin "C") (pinfunction "C_C") (pintype "passive"))
      (node (ref "D23") (pin "C") (pinfunction "C_C") (pintype "passive"))
      (node (ref "U4") (pin "18") (pinfunction "1C_18") (pintype "open_collector"))
    )
    (net (code "27") (name "LC_2") (class "Default")
      (node (ref "D12") (pin "C") (pinfunction "C_C") (pintype "passive"))
      (node (ref "D16") (pin "C") (pinfunction "C_C") (pintype "passive"))
      (node (ref "D20") (pin "C") (pinfunction "C_C") (pintype "passive"))
      (node (ref "D24") (pin "C") (pinfunction "C_C") (pintype "passive"))
      (node (ref "U4") (pin "17") (pinfunction "2C_17") (pintype "open_collector"))
    )
    (net (code "28") (name "LC_3") (class "Default")
      (node (ref "D13") (pin "C") (pinfunction "C_C") (pintype "passive"))
      (node (ref "D17") (pin "C") (pinfunction "C_C") (pintype "passive"))
      (node (ref "D21") (pin "C") (pinfunction "C_C") (pintype "passive"))
      (node (ref "D25") (pin "C") (pinfunction "C_C") (pintype "passive"))
      (node (ref "U4") (pin "16") (pinfunction "3C_16") (pintype "open_collector"))
    )
    (net (code "29") (name "LC_4") (class "Default")
      (node (ref "D14") (pin "C") (pinfunction "C_C") (pintype "passive"))
      (node (ref "D18") (pin "C") (pinfunction "C_C") (pintype "passive"))
      (node (ref "D22") (pin "C") (pinfunction "C_C") (pintype "passive"))
      (node (ref "D26") (pin "C") (pinfunction "C_C") (pintype "passive"))
      (node (ref "U4") (pin "15") (pinfunction "4C_15") (pintype "open_collector"))
    )
    (net (code "30") (name "LEDS_VCC") (class "Default")
      (node (ref "C15") (pin "1") (pinfunction "1_1") (pintype "passive"))
      (node (ref "Q1") (pin "2") (pinfunction "S2_2") (pintype "bidirectional"))
      (node (ref "Q1") (pin "5") (pinfunction "S1_5") (pintype "bidirectional"))
      (node (ref "Q2") (pin "2") (pinfunction "S2_2") (pintype "bidirectional"))
      (node (ref "Q2") (pin "5") (pinfunction "S1_5") (pintype "bidirectional"))
      (node (ref "R10") (pin "1") (pinfunction "1_1") (pintype "passive"))
      (node (ref "R11") (pin "1") (pinfunction "1_1") (pintype "passive"))
      (node (ref "R8") (pin "1") (pinfunction "1_1") (pintype "passive"))
      (node (ref "R9") (pin "1") (pinfunction "1_1") (pintype "passive"))
      (node (ref "VR2") (pin "5") (pinfunction "OUT_5") (pintype "power_in"))
    )
    (net (code "31") (name "LR_1_MI") (class "Default")
      (node (ref "Q1") (pin "1") (pinfunction "G1_1") (pintype "bidirectional"))
      (node (ref "R8") (pin "2") (pinfunction "2_2") (pintype "passive"))
      (node (ref "U1") (pin "29") (pinfunction "PB5_29") (pintype "bidirectional"))
    )
    (net (code "32") (name "LR_1_MO") (class "Default")
      (node (ref "D23") (pin "A") (pinfunction "A_A") (pintype "passive"))
      (node (ref "D24") (pin "A") (pinfunction "A_A") (pintype "passive"))
      (node (ref "D25") (pin "A") (pinfunction "A_A") (pintype "passive"))
      (node (ref "D26") (pin "A") (pinfunction "A_A") (pintype "passive"))
      (node (ref "R12") (pin "2") (pinfunction "2_2") (pintype "passive"))
    )
    (net (code "33") (name "LR_2_MI") (class "Default")
      (node (ref "Q1") (pin "3") (pinfunction "G2_3") (pintype "bidirectional"))
      (node (ref "R9") (pin "2") (pinfunction "2_2") (pintype "passive"))
      (node (ref "U1") (pin "30") (pinfunction "PB6_30") (pintype "bidirectional"))
    )
    (net (code "34") (name "LR_2_MO") (class "Default")
      (node (ref "D19") (pin "A") (pinfunction "A_A") (pintype "passive"))
      (node (ref "D20") (pin "A") (pinfunction "A_A") (pintype "passive"))
      (node (ref "D21") (pin "A") (pinfunction "A_A") (pintype "passive"))
      (node (ref "D22") (pin "A") (pinfunction "A_A") (pintype "passive"))
      (node (ref "R13") (pin "2") (pinfunction "2_2") (pintype "passive"))
    )
    (net (code "35") (name "LR_3_MI") (class "Default")
      (node (ref "Q2") (pin "1") (pinfunction "G1_1") (pintype "bidirectional"))
      (node (ref "R10") (pin "2") (pinfunction "2_2") (pintype "passive"))
      (node (ref "U1") (pin "31") (pinfunction "PC6_31") (pintype "bidirectional"))
    )
    (net (code "36") (name "LR_3_MO") (class "Default")
      (node (ref "D11") (pin "A") (pinfunction "A_A") (pintype "passive"))
      (node (ref "D12") (pin "A") (pinfunction "A_A") (pintype "passive"))
      (node (ref "D13") (pin "A") (pinfunction "A_A") (pintype "passive"))
      (node (ref "D14") (pin "A") (pinfunction "A_A") (pintype "passive"))
      (node (ref "R14") (pin "2") (pinfunction "2_2") (pintype "passive"))
    )
    (net (code "37") (name "LR_4_MI") (class "Default")
      (node (ref "Q2") (pin "3") (pinfunction "G2_3") (pintype "bidirectional"))
      (node (ref "R11") (pin "2") (pinfunction "2_2") (pintype "passive"))
      (node (ref "U1") (pin "32") (pinfunction "PC7_32") (pintype "bidirectional"))
    )
    (net (code "38") (name "LR_4_MO") (class "Default")
      (node (ref "D15") (pin "A") (pinfunction "A_A") (pintype "passive"))
      (node (ref "D16") (pin "A") (pinfunction "A_A") (pintype "passive"))
      (node (ref "D17") (pin "A") (pinfunction "A_A") (pintype "passive"))
      (node (ref "D18") (pin "A") (pinfunction "A_A") (pintype "passive"))
      (node (ref "R15") (pin "2") (pinfunction "2_2") (pintype "passive"))
    )
    (net (code "39") (name "MISO") (class "Default")
      (node (ref "CONN1") (pin "1") (pinfunction "1_1") (pintype "passive"))
      (node (ref "U1") (pin "11") (pinfunction "PB3_11") (pintype "bidirectional"))
    )
    (net (code "40") (name "MOSI") (class "Default")
      (node (ref "CONN1") (pin "4") (pinfunction "4_4") (pintype "passive"))
      (node (ref "U1") (pin "10") (pinfunction "PB2_10") (pintype "bidirectional"))
    )
    (net (code "41") (name "MUX_COMMON_1") (class "Default")
      (node (ref "CONN6") (pin "3") (pinfunction "3_3") (pintype "passive"))
      (node (ref "U1") (pin "40") (pinfunction "PF1_40") (pintype "bidirectional"))
    )
    (net (code "42") (name "MUX_S0_3V3") (class "Default")
      (node (ref "CONN6") (pin "8") (pinfunction "8_8") (pintype "passive"))
      (node (ref "U5") (pin "11") (pinfunction "4Y_11") (pintype "bidirectional"))
    )
    (net (code "43") (name "MUX_S0_5V") (class "Default")
      (node (ref "U1") (pin "37") (pinfunction "PF6_37") (pintype "bidirectional"))
      (node (ref "U5") (pin "12") (pinfunction "4A_12") (pintype "bidirectional"))
    )
    (net (code "44") (name "MUX_S1_3V3") (class "Default")
      (node (ref "CONN6") (pin "7") (pinfunction "7_7") (pintype "passive"))
      (node (ref "U5") (pin "8") (pinfunction "3Y_8") (pintype "bidirectional"))
    )
    (net (code "45") (name "MUX_S1_5V") (class "Default")
      (node (ref "U1") (pin "38") (pinfunction "PF5_38") (pintype "bidirectional"))
      (node (ref "U5") (pin "9") (pinfunction "3A_9") (pintype "bidirectional"))
    )
    (net (code "46") (name "MUX_S2_3V3") (class "Default")
      (node (ref "CONN6") (pin "5") (pinfunction "5_5") (pintype "passive"))
      (node (ref "U5") (pin "3") (pinfunction "1Y_3") (pintype "bidirectional"))
    )
    (net (code "47") (name "MUX_S2_5V") (class "Default")
      (node (ref "U1") (pin "36") (pinfunction "PF7_36") (pintype "bidirectional"))
      (node (ref "U5") (pin "2") (pinfunction "1A_2") (pintype "bidirectional"))
    )
    (net (code "48") (name "MUX_S3_3V3") (class "Default")
      (node (ref "CONN6") (pin "6") (pinfunction "6_6") (pintype "passive"))
      (node (ref "U5") (pin "6") (pinfunction "2Y_6") (pintype "bidirectional"))
    )
    (net (code "49") (name "MUX_S3_5V") (class "Default")
      (node (ref "U1") (pin "39") (pinfunction "PF4_39") (pintype "bidirectional"))
      (node (ref "U5") (pin "5") (pinfunction "2A_5") (pintype "bidirectional"))
    )
    (net (code "50") (name "Net-(CONN2-Pad5)") (class "Default")
      (node (ref "CONN2") (pin "5") (pinfunction "5_5") (pintype "passive"))
      (node (ref "L1") (pin "2") (pinfunction "2_2") (pintype "passive"))
    )
    (net (code "51") (name "Net-(D1-Pad1)") (class "Default")
      (node (ref "D1") (pin "1") (pinfunction "1_1") (pintype "passive"))
      (node (ref "SW2") (pin "1") (pinfunction "1_1") (pintype "passive"))
    )
    (net (code "52") (name "Net-(D1-Pad2)") (class "Default")
      (node (ref "D1") (pin "2") (pinfunction "2_2") (pintype "passive"))
      (node (ref "SW1") (pin "1") (pinfunction "1_1") (pintype "passive"))
    )
    (net (code "53") (name "Net-(D2-Pad1)") (class "Default")
      (node (ref "D2") (pin "1") (pinfunction "1_1") (pintype "passive"))
      (node (ref "SW4") (pin "1") (pinfunction "1_1") (pintype "passive"))
    )
    (net (code "54") (name "Net-(D2-Pad2)") (class "Default")
      (node (ref "D2") (pin "2") (pinfunction "2_2") (pintype "passive"))
      (node (ref "SW3") (pin "1") (pinfunction "1_1") (pintype "passive"))
    )
    (net (code "55") (name "Net-(D3-Pad1)") (class "Default")
      (node (ref "D3") (pin "1") (pinfunction "1_1") (pintype "passive"))
      (node (ref "SW6") (pin "1") (pinfunction "1_1") (pintype "passive"))
    )
    (net (code "56") (name "Net-(D3-Pad2)") (class "Default")
      (node (ref "D3") (pin "2") (pinfunction "2_2") (pintype "passive"))
      (node (ref "SW5") (pin "1") (pinfunction "1_1") (pintype "passive"))
    )
    (net (code "57") (name "Net-(D4-Pad1)") (class "Default")
      (node (ref "D4") (pin "1") (pinfunction "1_1") (pintype "passive"))
      (node (ref "SW8") (pin "1") (pinfunction "1_1") (pintype "passive"))
    )
    (net (code "58") (name "Net-(D4-Pad2)") (class "Default")
      (node (ref "D4") (pin "2") (pinfunction "2_2") (pintype "passive"))
      (node (ref "SW7") (pin "1") (pinfunction "1_1") (pintype "passive"))
    )
    (net (code "59") (name "Net-(D5-Pad1)") (class "Default")
      (node (ref "D5") (pin "1") (pinfunction "1_1") (pintype "passive"))
      (node (ref "SW10") (pin "1") (pinfunction "1_1") (pintype "passive"))
    )
    (net (code "60") (name "Net-(D5-Pad2)") (class "Default")
      (node (ref "D5") (pin "2") (pinfunction "2_2") (pintype "passive"))
      (node (ref "SW9") (pin "1") (pinfunction "1_1") (pintype "passive"))
    )
    (net (code "61") (name "Net-(D6-Pad1)") (class "Default")
      (node (ref "D6") (pin "1") (pinfunction "1_1") (pintype "passive"))
      (node (ref "SW12") (pin "1") (pinfunction "1_1") (pintype "passive"))
    )
    (net (code "62") (name "Net-(D6-Pad2)") (class "Default")
      (node (ref "D6") (pin "2") (pinfunction "2_2") (pintype "passive"))
      (node (ref "SW11") (pin "1") (pinfunction "1_1") (pintype "passive"))
    )
    (net (code "63") (name "Net-(D7-Pad1)") (class "Default")
      (node (ref "D7") (pin "1") (pinfunction "1_1") (pintype "passive"))
      (node (ref "SW14") (pin "1") (pinfunction "1_1") (pintype "passive"))
    )
    (net (code "64") (name "Net-(D7-Pad2)") (class "Default")
      (node (ref "D7") (pin "2") (pinfunction "2_2") (pintype "passive"))
      (node (ref "SW13") (pin "1") (pinfunction "1_1") (pintype "passive"))
    )
    (net (code "65") (name "Net-(D8-Pad1)") (class "Default")
      (node (ref "D8") (pin "1") (pinfunction "1_1") (pintype "passive"))
      (node (ref "SW16") (pin "1") (pinfunction "1_1") (pintype "passive"))
    )
    (net (code "66") (name "Net-(D8-Pad2)") (class "Default")
      (node (ref "D8") (pin "2") (pinfunction "2_2") (pintype "passive"))
      (node (ref "SW15") (pin "1") (pinfunction "1_1") (pintype "passive"))
    )
    (net (code "67") (name "Net-(Q1-D1)") (class "Default")
      (node (ref "Q1") (pin "6") (pinfunction "D1_6") (pintype "bidirectional"))
      (node (ref "R12") (pin "1") (pinfunction "1_1") (pintype "passive"))
    )
    (net (code "68") (name "Net-(Q1-D2)") (class "Default")
      (node (ref "Q1") (pin "4") (pinfunction "D2_4") (pintype "bidirectional"))
      (node (ref "R13") (pin "1") (pinfunction "1_1") (pintype "passive"))
    )
    (net (code "69") (name "Net-(Q2-D1)") (class "Default")
      (node (ref "Q2") (pin "6") (pinfunction "D1_6") (pintype "bidirectional"))
      (node (ref "R14") (pin "1") (pinfunction "1_1") (pintype "passive"))
    )
    (net (code "70") (name "Net-(Q2-D2)") (class "Default")
      (node (ref "Q2") (pin "4") (pinfunction "D2_4") (pintype "bidirectional"))
      (node (ref "R15") (pin "1") (pinfunction "1_1") (pintype "passive"))
    )
    (net (code "71") (name "Net-(U1-UCAP)") (class "Default")
      (node (ref "C1") (pin "1") (pinfunction "1_1") (pintype "passive"))
      (node (ref "U1") (pin "6") (pinfunction "UCAP_6") (pintype "passive"))
    )
    (net (code "72") (name "Net-(U3-Y0)") (class "Default")
      (node (ref "U3") (pin "15") (pinfunction "Y0_15") (pintype "output"))
      (node (ref "U4") (pin "1") (pinfunction "1B_1") (pintype "input"))
    )
    (net (code "73") (name "Net-(U3-Y1)") (class "Default")
      (node (ref "U3") (pin "14") (pinfunction "Y1_14") (pintype "output"))
      (node (ref "U4") (pin "2") (pinfunction "2B_2") (pintype "input"))
    )
    (net (code "74") (name "Net-(U3-Y2)") (class "Default")
      (node (ref "U3") (pin "13") (pinfunction "Y2_13") (pintype "output"))
      (node (ref "U4") (pin "3") (pinfunction "3B_3") (pintype "input"))
    )
    (net (code "75") (name "Net-(U3-Y3)") (class "Default")
      (node (ref "U3") (pin "12") (pinfunction "Y3_12") (pintype "output"))
      (node (ref "U4") (pin "4") (pinfunction "4B_4") (pintype "input"))
    )
    (net (code "76") (name "Net-(U3-Y4)") (class "Default")
      (node (ref "U3") (pin "11") (pinfunction "Y4_11") (pintype "output"))
      (node (ref "U4") (pin "5") (pinfunction "5B_5") (pintype "input"))
    )
    (net (code "77") (name "Net-(U3-Y5)") (class "Default")
      (node (ref "U3") (pin "10") (pinfunction "Y5_10") (pintype "output"))
      (node (ref "U4") (pin "6") (pinfunction "6B_6") (pintype "input"))
    )
    (net (code "78") (name "Net-(U3-Y6)") (class "Default")
      (node (ref "U3") (pin "9") (pinfunction "Y6_9") (pintype "output"))
      (node (ref "U4") (pin "7") (pinfunction "7B_7") (pintype "input"))
    )
    (net (code "79") (name "Net-(U3-Y7)") (class "Default")
      (node (ref "U3") (pin "7") (pinfunction "Y7_7") (pintype "output"))
      (node (ref "U4") (pin "8") (pinfunction "8B_8") (pintype "input"))
    )
    (net (code "80") (name "RESET") (class "Default")
      (node (ref "CONN1") (pin "5") (pinfunction "5_5") (pintype "passive"))
      (node (ref "R1") (pin "1") (pinfunction "1_1") (pintype "passive"))
      (node (ref "U1") (pin "13") (pinfunction "~{RESET}_13") (pintype "input"))
    )
    (net (code "81") (name "SCK") (class "Default")
      (node (ref "CONN1") (pin "3") (pinfunction "3_3") (pintype "passive"))
      (node (ref "U1") (pin "9") (pinfunction "PB1_9") (pintype "bidirectional"))
    )
    (net (code "82") (name "SR_IN_CLK") (class "Default")
      (node (ref "U1") (pin "21") (pinfunction "PD3_21") (pintype "bidirectional"))
      (node (ref "U2") (pin "2") (pinfunction "CP_2") (pintype "bidirectional"))
    )
    (net (code "83") (name "SR_IN_DATA") (class "Default")
      (node (ref "U1") (pin "25") (pinfunction "PD4_25") (pintype "bidirectional"))
      (node (ref "U2") (pin "9") (pinfunction "Q7_9") (pintype "output"))
    )
    (net (code "84") (name "SR_IN_PL") (class "Default")
      (node (ref "U1") (pin "22") (pinfunction "PD5_22") (pintype "bidirectional"))
      (node (ref "U2") (pin "1") (pinfunction "~{PL}_1") (pintype "input"))
    )
    (net (code "85") (name "SW_M_11") (class "Default")
      (node (ref "CONN3") (pin "1") (pinfunction "1_1") (pintype "passive"))
      (node (ref "D9") (pin "2") (pinfunction "2_2") (pintype "passive"))
    )
    (net (code "86") (name "SW_M_21") (class "Default")
      (node (ref "CONN4") (pin "1") (pinfunction "1_1") (pintype "passive"))
      (node (ref "D9") (pin "1") (pinfunction "1_1") (pintype "passive"))
    )
    (net (code "87") (name "SW_M_31") (class "Default")
      (node (ref "CONN5") (pin "1") (pinfunction "1_1") (pintype "passive"))
      (node (ref "D10") (pin "2") (pinfunction "2_2") (pintype "passive"))
    )
    (net (code "88") (name "XTAL1") (class "Default")
      (node (ref "C10") (pin "2") (pinfunction "2_2") (pintype "passive"))
      (node (ref "U1") (pin "17") (pinfunction "XTAL1_17") (pintype "bidirectional"))
      (node (ref "Y1") (pin "1") (pinfunction "1_1") (pintype "passive"))
    )
    (net (code "89") (name "XTAL2") (class "Default")
      (node (ref "C11") (pin "2") (pinfunction "2_2") (pintype "passive"))
      (node (ref "U1") (pin "16") (pinfunction "XTAL2_16") (pintype "bidirectional"))
      (node (ref "Y1") (pin "2") (pinfunction "2_2") (pintype "passive"))
    )
    (net (code "90") (name "unconnected-(D10-Pad1)") (class "Default")
      (node (ref "D10") (pin "1") (pinfunction "1_1") (pintype "passive"))
    )
    (net (code "91") (name "unconnected-(U1-PB0-Pad8)") (class "Default")
      (node (ref "U1") (pin "8") (pinfunction "PB0_8") (pintype "bidirectional"))
    )
    (net (code "92") (name "unconnected-(U1-PB7-Pad12)") (class "Default")
      (node (ref "U1") (pin "12") (pinfunction "PB7_12") (pintype "bidirectional"))
    )
    (net (code "93") (name "unconnected-(U1-PE2-Pad33)") (class "Default")
      (node (ref "U1") (pin "33") (pinfunction "PE2_33") (pintype "bidirectional"))
    )
    (net (code "94") (name "unconnected-(U1-PE6-Pad1)") (class "Default")
      (node (ref "U1") (pin "1") (pinfunction "PE6_1") (pintype "bidirectional"))
    )
    (net (code "95") (name "unconnected-(U1-PF0-Pad41)") (class "Default")
      (node (ref "U1") (pin "41") (pinfunction "PF0_41") (pintype "bidirectional"))
    )
    (net (code "96") (name "unconnected-(U2-DS-Pad10)") (class "Default")
      (node (ref "U2") (pin "10") (pinfunction "DS_10") (pintype "bidirectional"))
    )
    (net (code "97") (name "unconnected-(U2-~{Q7}-Pad7)") (class "Default")
      (node (ref "U2") (pin "7") (pinfunction "~{Q7}_7") (pintype "output"))
    )
    (net (code "98") (name "unconnected-(U4-5C-Pad14)") (class "Default")
      (node (ref "U4") (pin "14") (pinfunction "5C_14") (pintype "open_collector"))
    )
    (net (code "99") (name "unconnected-(U4-6C-Pad13)") (class "Default")
      (node (ref "U4") (pin "13") (pinfunction "6C_13") (pintype "open_collector"))
    )
    (net (code "100") (name "unconnected-(U4-7C-Pad12)") (class "Default")
      (node (ref "U4") (pin "12") (pinfunction "7C_12") (pintype "open_collector"))
    )
    (net (code "101") (name "unconnected-(U4-8C-Pad11)") (class "Default")
      (node (ref "U4") (pin "11") (pinfunction "8C_11") (pintype "open_collector"))
    )
    (net (code "102") (name "unconnected-(VR2-NC-Pad4)") (class "Default")
      (node (ref "VR2") (pin "4") (pinfunction "NC_4") (pintype "no_connect"))
    )
  )
)
